# Sirena_555_version_final.net
KiCad netlist of a schematic drawn in EAGLE
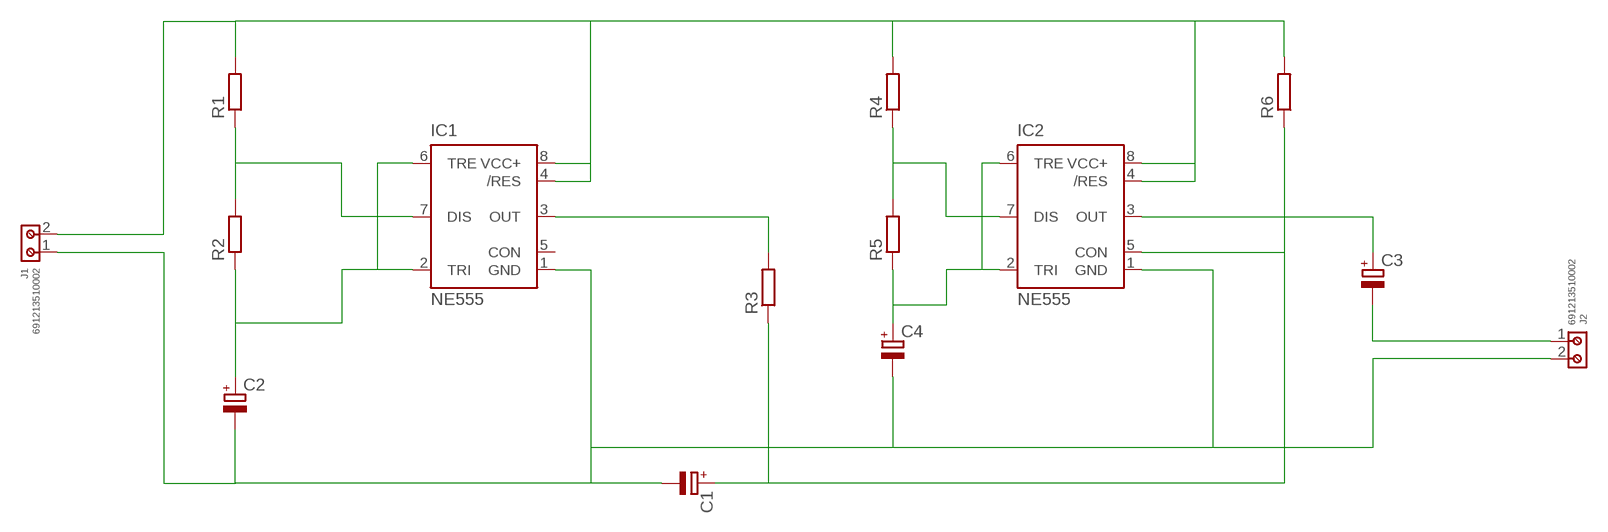
[diagram p0: schematic, sheet 1]

(export (version "E")
  (design (tool "Eeschema 10.0.6"))
  (components
    (comp (ref "C1")
      (value "CPOL-EUE3.5-10")
      (footprint "eagle-import:E3,5-10")
      (libsource (lib "eagle-import") (part "CPOL-EUE3.5-10"))
    )
    (comp (ref "C2")
      (value "CPOL-EUE2.5-5")
      (footprint "eagle-import:E2,5-5")
      (libsource (lib "eagle-import") (part "CPOL-EUE2.5-5"))
    )
    (comp (ref "C3")
      (value "CPOL-EUE2.5-5")
      (footprint "eagle-import:E2,5-5")
      (libsource (lib "eagle-import") (part "CPOL-EUE2.5-5"))
    )
    (comp (ref "C4")
      (value "CPOL-EUE2-4")
      (footprint "eagle-import:E2-4")
      (libsource (lib "eagle-import") (part "CPOL-EUE2-4"))
    )
    (comp (ref "IC1")
      (value "NE555")
      (footprint "eagle-import:DIL-08")
      (fields (field (name "MF") "Arrow Electronics") (field (name "MPN") "NE555N"))
      (libsource (lib "eagle-import") (part "NE555"))
    )
    (comp (ref "IC2")
      (value "NE555")
      (footprint "eagle-import:DIL-08")
      (fields (field (name "MF") "Arrow Electronics") (field (name "MPN") "NE555N"))
      (libsource (lib "eagle-import") (part "NE555"))
    )
    (comp (ref "J1")
      (value "691213510002")
      (footprint "eagle-import:691213510002")
      (fields (field (name "MF") "Wurth Electronics"))
      (libsource (lib "eagle-import") (part "691213510002"))
    )
    (comp (ref "J2")
      (value "691213510002")
      (footprint "eagle-import:691213510002")
      (fields (field (name "MF") "Wurth Electronics"))
      (libsource (lib "eagle-import") (part "691213510002"))
    )
    (comp (ref "R1")
      (value "R-EU_0309/12")
      (footprint "eagle-import:0309_12")
      (libsource (lib "eagle-import") (part "R-EU_0309/12"))
    )
    (comp (ref "R2")
      (value "R-EU_0309/12")
      (footprint "eagle-import:0309_12")
      (libsource (lib "eagle-import") (part "R-EU_0309/12"))
    )
    (comp (ref "R3")
      (value "R-EU_0309/12")
      (footprint "eagle-import:0309_12")
      (libsource (lib "eagle-import") (part "R-EU_0309/12"))
    )
    (comp (ref "R4")
      (value "R-EU_0309/12")
      (footprint "eagle-import:0309_12")
      (libsource (lib "eagle-import") (part "R-EU_0309/12"))
    )
    (comp (ref "R5")
      (value "R-EU_0309/12")
      (footprint "eagle-import:0309_12")
      (libsource (lib "eagle-import") (part "R-EU_0309/12"))
    )
    (comp (ref "R6")
      (value "R-EU_0309/12")
      (footprint "eagle-import:0309_12")
      (libsource (lib "eagle-import") (part "R-EU_0309/12"))
    )
  )
  (nets
    (net (code "1") (name "Net-(C3-Pad-)") (class "Default")
      (node (ref "C3") (pin "-") (pinfunction "-_-") (pintype "passive"))
      (node (ref "J2") (pin "1") (pinfunction "1_1") (pintype "passive"))
    )
    (net (code "2") (name "Net-(IC1-DIS)") (class "Default")
      (node (ref "IC1") (pin "7") (pinfunction "DIS_7") (pintype "input"))
      (node (ref "R1") (pin "1") (pinfunction "1_1") (pintype "passive"))
      (node (ref "R2") (pin "2") (pinfunction "2_2") (pintype "passive"))
    )
    (net (code "3") (name "Net-(IC1-GND)") (class "Default")
      (node (ref "C1") (pin "-") (pinfunction "-_-") (pintype "passive"))
      (node (ref "C2") (pin "-") (pinfunction "-_-") (pintype "passive"))
      (node (ref "C4") (pin "-") (pinfunction "-_-") (pintype "passive"))
      (node (ref "IC1") (pin "1") (pinfunction "GND_1") (pintype "power_in"))
      (node (ref "IC2") (pin "1") (pinfunction "GND_1") (pintype "power_in"))
      (node (ref "J1") (pin "1") (pinfunction "1_1") (pintype "passive"))
      (node (ref "J2") (pin "2") (pinfunction "2_2") (pintype "passive"))
    )
    (net (code "4") (name "Net-(IC1-OUT)") (class "Default")
      (node (ref "IC1") (pin "3") (pinfunction "OUT_3") (pintype "output"))
      (node (ref "R3") (pin "2") (pinfunction "2_2") (pintype "passive"))
    )
    (net (code "5") (name "Net-(IC1-TRE)") (class "Default")
      (node (ref "C2") (pin "+") (pinfunction "+_+") (pintype "passive"))
      (node (ref "IC1") (pin "2") (pinfunction "TRI_2") (pintype "input"))
      (node (ref "IC1") (pin "6") (pinfunction "TRE_6") (pintype "input"))
      (node (ref "R2") (pin "1") (pinfunction "1_1") (pintype "passive"))
    )
    (net (code "6") (name "Net-(IC1-VCC+)") (class "Default")
      (node (ref "IC1") (pin "4") (pinfunction "/RES_4") (pintype "input"))
      (node (ref "IC1") (pin "8") (pinfunction "VCC+_8") (pintype "power_in"))
      (node (ref "IC2") (pin "4") (pinfunction "/RES_4") (pintype "input"))
      (node (ref "IC2") (pin "8") (pinfunction "VCC+_8") (pintype "power_in"))
      (node (ref "J1") (pin "2") (pinfunction "2_2") (pintype "passive"))
      (node (ref "R1") (pin "2") (pinfunction "2_2") (pintype "passive"))
      (node (ref "R4") (pin "2") (pinfunction "2_2") (pintype "passive"))
      (node (ref "R6") (pin "2") (pinfunction "2_2") (pintype "passive"))
    )
    (net (code "7") (name "Net-(IC2-CON)") (class "Default")
      (node (ref "C1") (pin "+") (pinfunction "+_+") (pintype "passive"))
      (node (ref "IC2") (pin "5") (pinfunction "CON_5") (pintype "input"))
      (node (ref "R3") (pin "1") (pinfunction "1_1") (pintype "passive"))
      (node (ref "R6") (pin "1") (pinfunction "1_1") (pintype "passive"))
    )
    (net (code "8") (name "Net-(IC2-DIS)") (class "Default")
      (node (ref "IC2") (pin "7") (pinfunction "DIS_7") (pintype "input"))
      (node (ref "R4") (pin "1") (pinfunction "1_1") (pintype "passive"))
      (node (ref "R5") (pin "2") (pinfunction "2_2") (pintype "passive"))
    )
    (net (code "9") (name "Net-(IC2-OUT)") (class "Default")
      (node (ref "C3") (pin "+") (pinfunction "+_+") (pintype "passive"))
      (node (ref "IC2") (pin "3") (pinfunction "OUT_3") (pintype "output"))
    )
    (net (code "10") (name "Net-(IC2-TRE)") (class "Default")
      (node (ref "C4") (pin "+") (pinfunction "+_+") (pintype "passive"))
      (node (ref "IC2") (pin "2") (pinfunction "TRI_2") (pintype "input"))
      (node (ref "IC2") (pin "6") (pinfunction "TRE_6") (pintype "input"))
      (node (ref "R5") (pin "1") (pinfunction "1_1") (pintype "passive"))
    )
    (net (code "11") (name "unconnected-(IC1-CON-Pad5)") (class "Default")
      (node (ref "IC1") (pin "5") (pinfunction "CON_5") (pintype "input"))
    )
  )
)
